# Printrhub_Rev_0_4.net
KiCad netlist of a schematic drawn in EAGLE
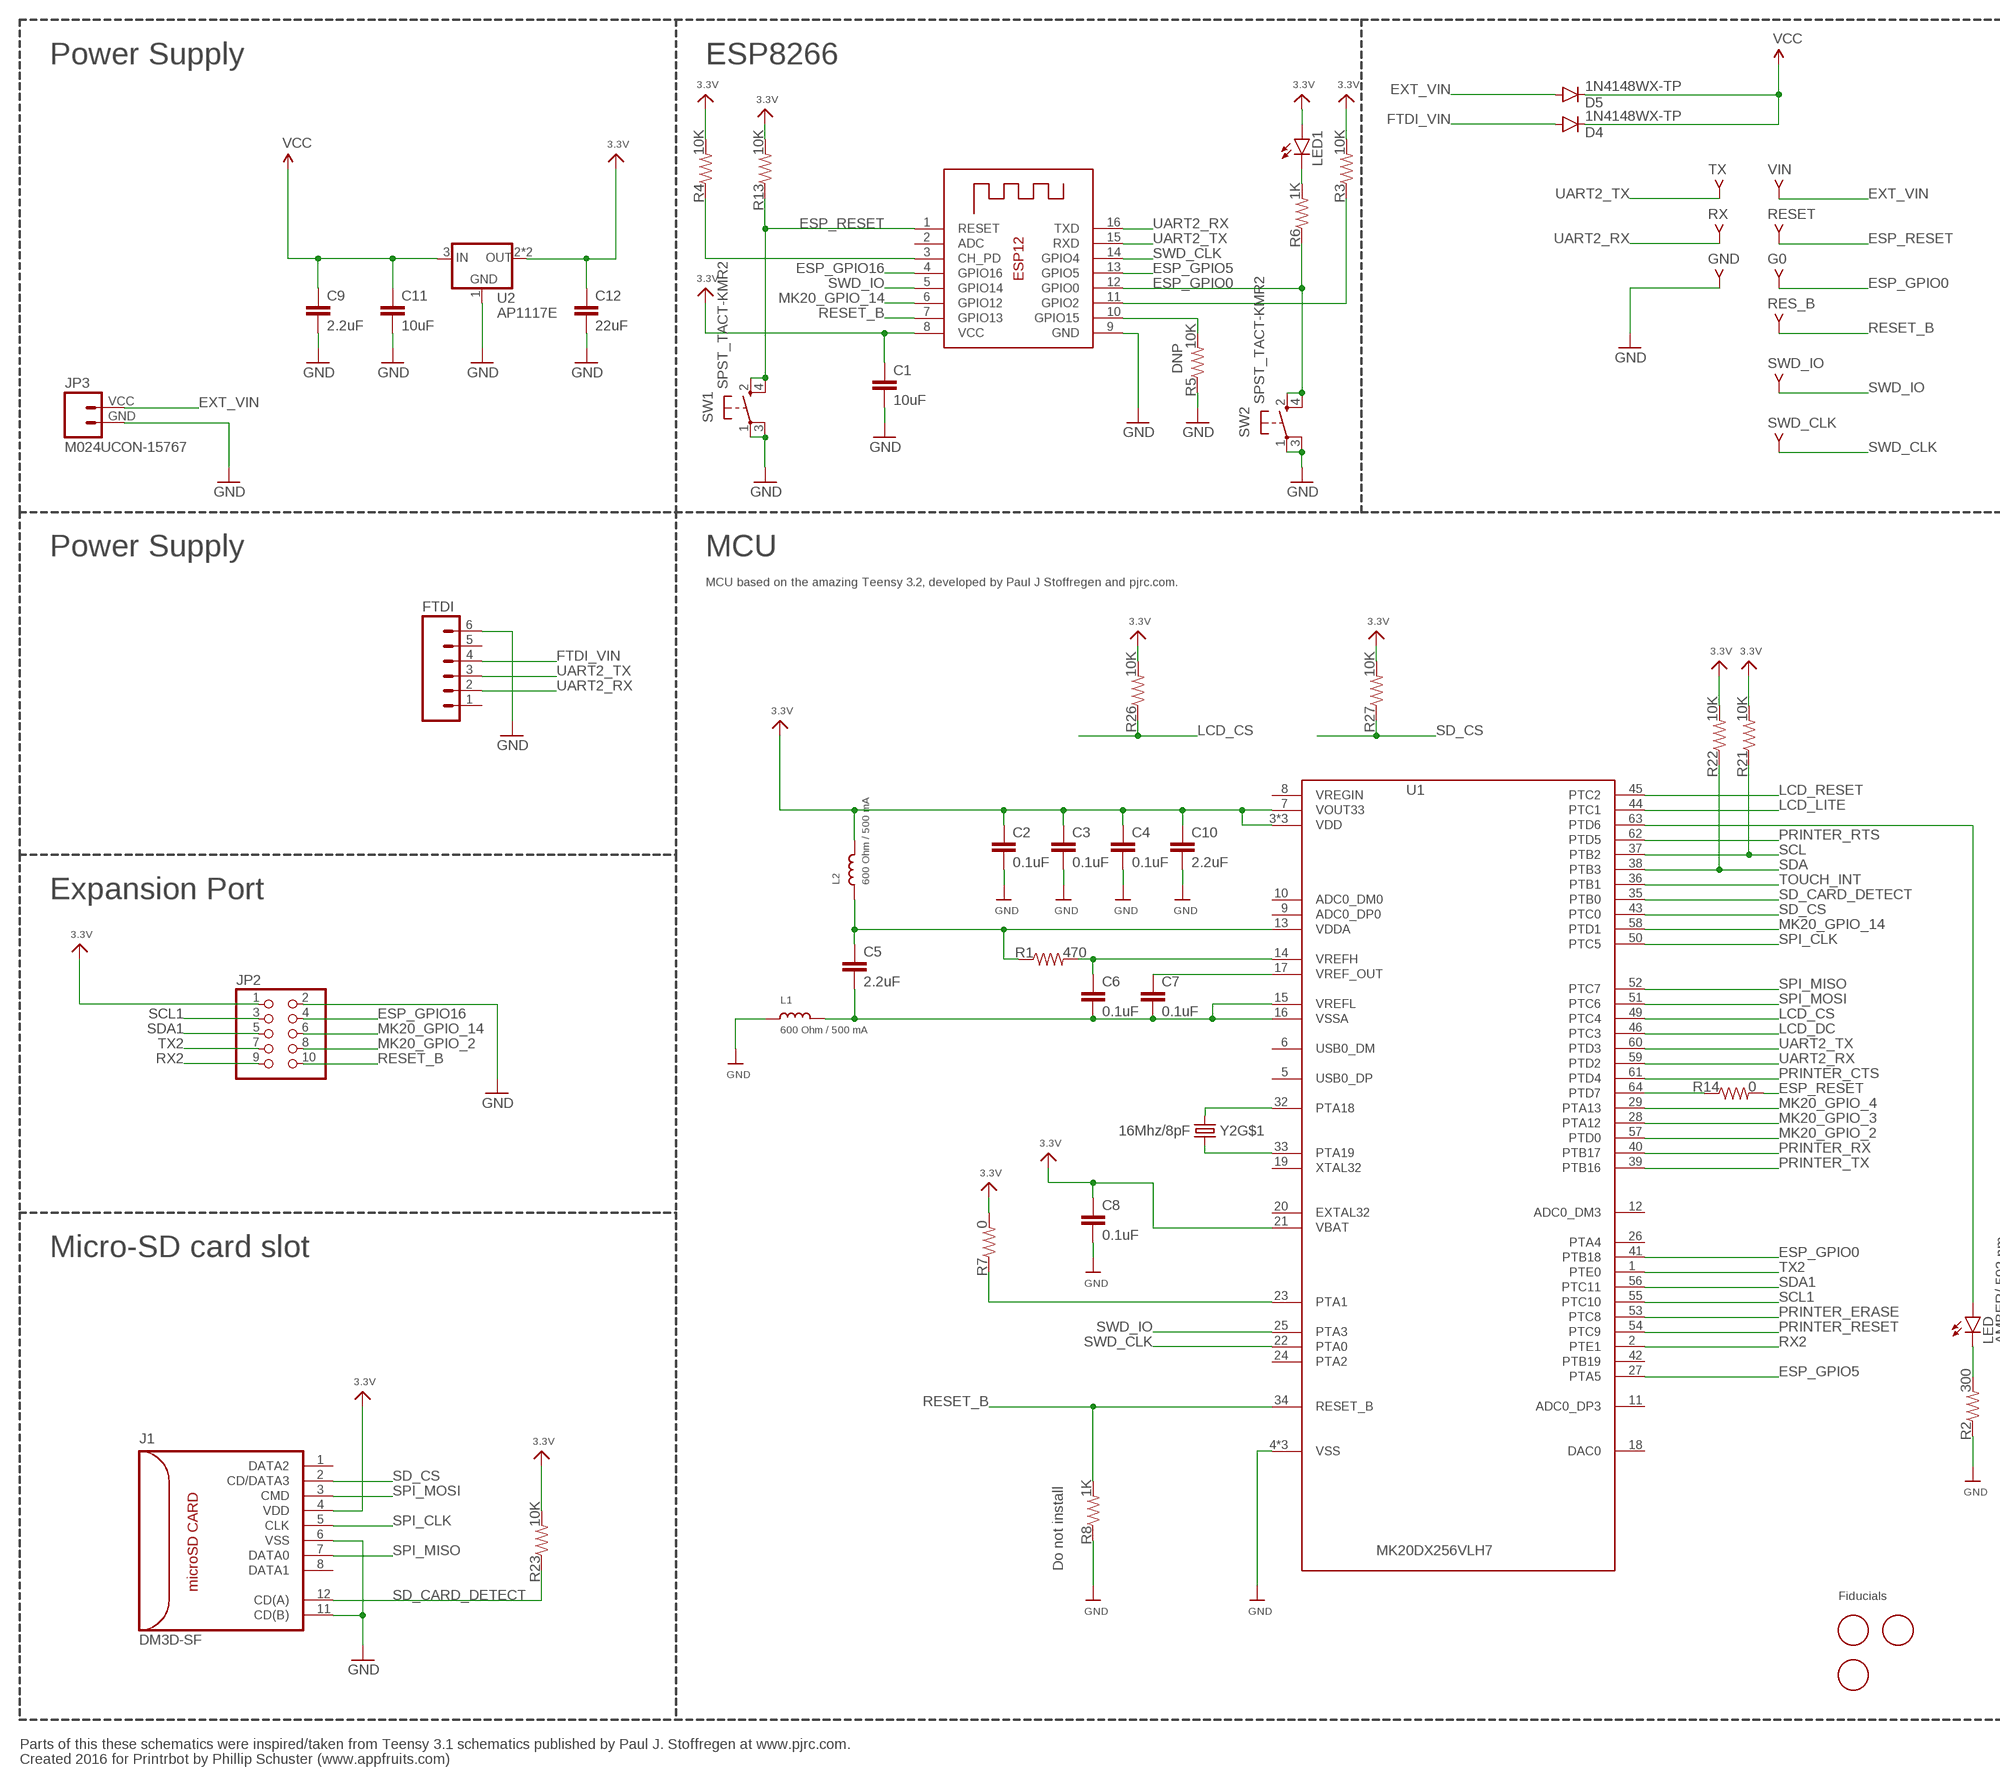
[diagram p0: schematic, sheet 1, part 1 of 2]
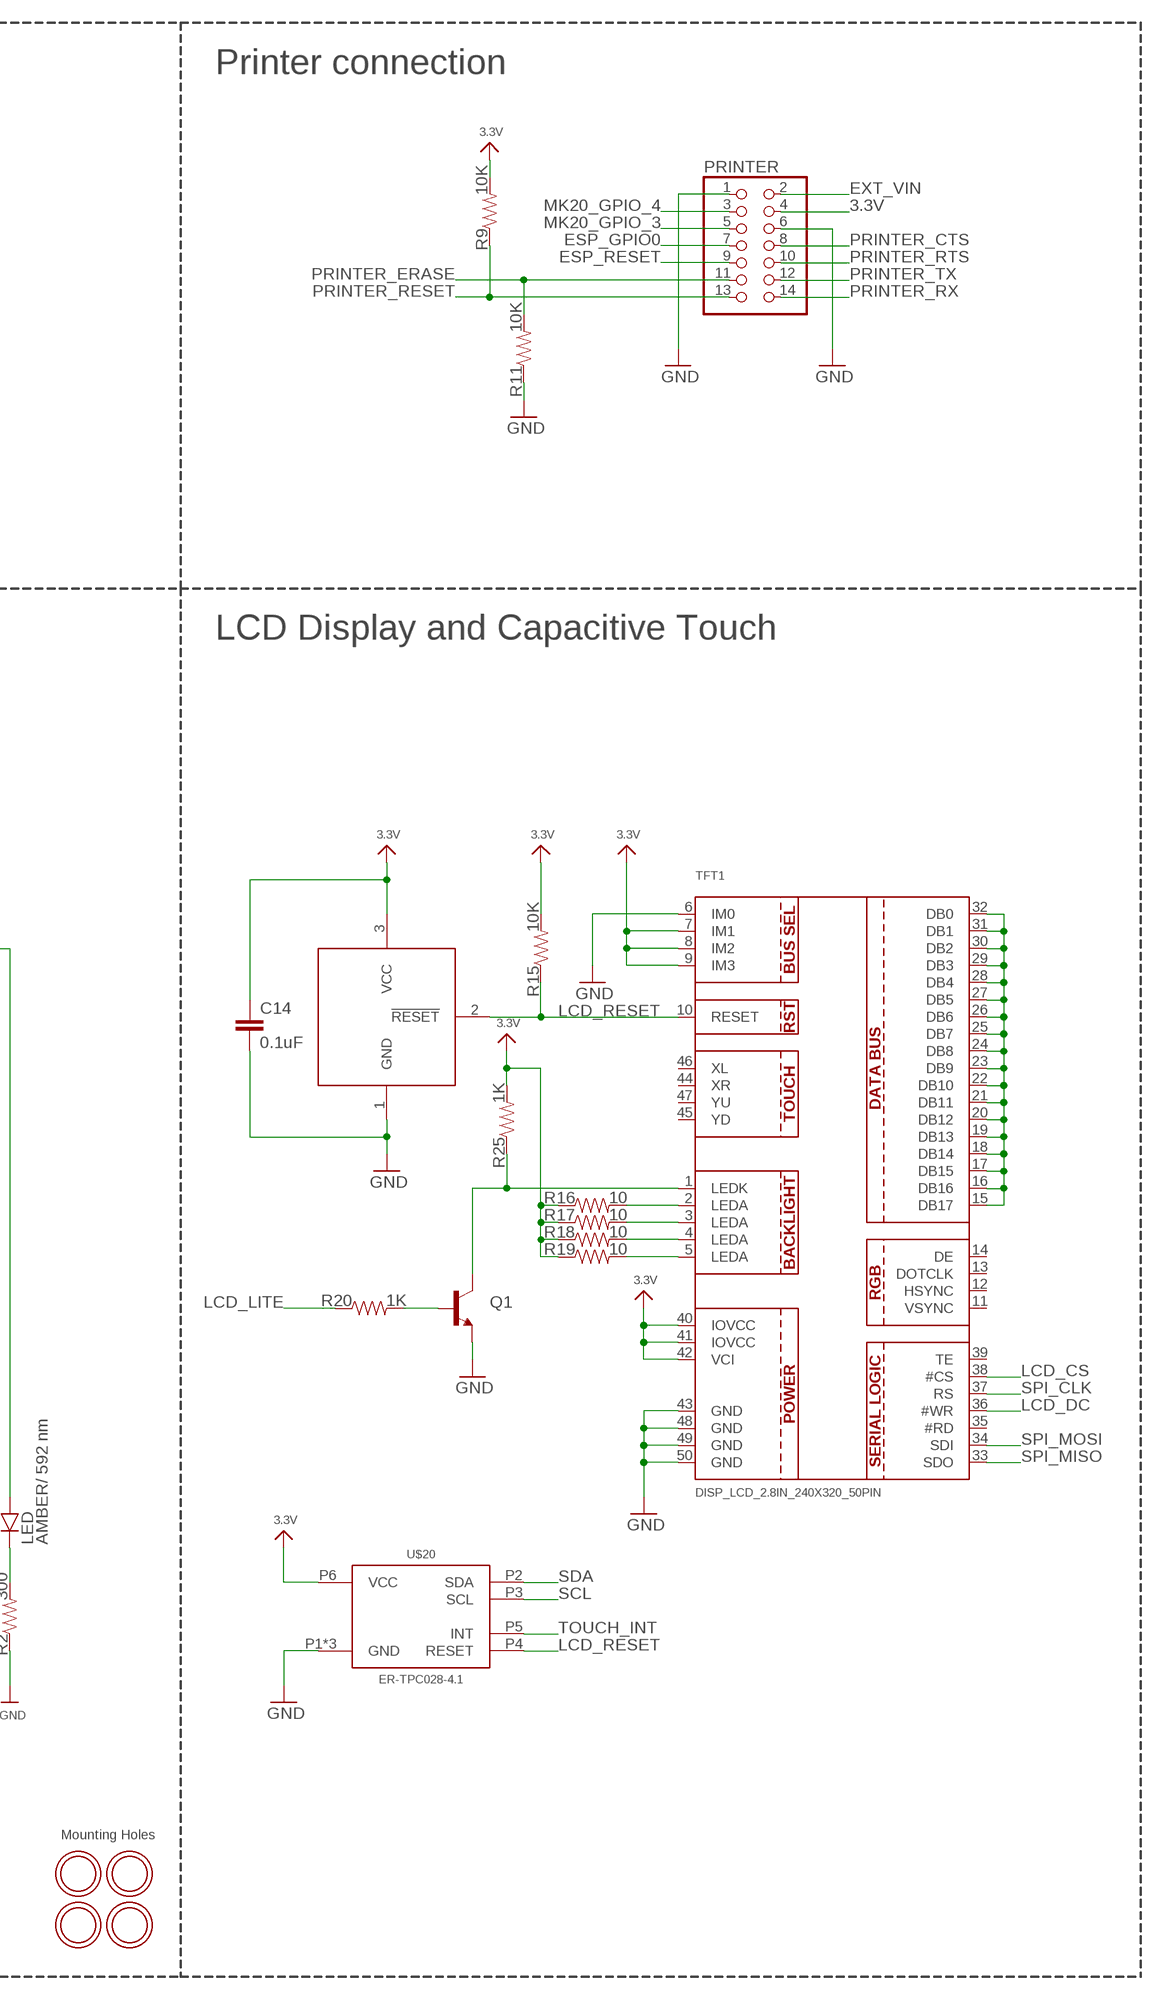
[diagram p1: schematic, sheet 1, part 2 of 2]

(export (version "E")
  (design (tool "Eeschema 10.0.6"))
  (components
    (comp (ref "C1")
      (value "10uF")
      (footprint "eagle-import:0603-CAP")
      (fields (field (name "MF") "Murata") (field (name "MPN") "GRM188R60J106ME47D"))
      (libsource (lib "eagle-import") (part "CAPACITOR-10UF"))
    )
    (comp (ref "C2")
      (value "0.1uF")
      (footprint "eagle-import:0603-CAP")
      (fields (field (name "MF") "Kemet") (field (name "MPN") "C0603C104J3RACTU"))
      (libsource (lib "eagle-import") (part "CAPACITOR-0.1UF"))
    )
    (comp (ref "C3")
      (value "0.1uF")
      (footprint "eagle-import:0603-CAP")
      (fields (field (name "MF") "Kemet") (field (name "MPN") "C0603C104J3RACTU"))
      (libsource (lib "eagle-import") (part "CAPACITOR-0.1UF"))
    )
    (comp (ref "C4")
      (value "0.1uF")
      (footprint "eagle-import:0603-CAP")
      (fields (field (name "MF") "Kemet") (field (name "MPN") "C0603C104J3RACTU"))
      (libsource (lib "eagle-import") (part "CAPACITOR-0.1UF"))
    )
    (comp (ref "C5")
      (value "2.2uF")
      (footprint "eagle-import:0603-CAP")
      (fields (field (name "MF") "Kemet") (field (name "MPN") "C0603C225K4PACTU"))
      (libsource (lib "eagle-import") (part "CAPACITOR-2.2UF"))
    )
    (comp (ref "C6")
      (value "0.1uF")
      (footprint "eagle-import:0603-CAP")
      (fields (field (name "MF") "Kemet") (field (name "MPN") "C0603C104J3RACTU"))
      (libsource (lib "eagle-import") (part "CAPACITOR-0.1UF"))
    )
    (comp (ref "C7")
      (value "0.1uF")
      (footprint "eagle-import:0603-CAP")
      (fields (field (name "MF") "Kemet") (field (name "MPN") "C0603C104J3RACTU"))
      (libsource (lib "eagle-import") (part "CAPACITOR-0.1UF"))
    )
    (comp (ref "C8")
      (value "0.1uF")
      (footprint "eagle-import:0603-CAP")
      (fields (field (name "MF") "Kemet") (field (name "MPN") "C0603C104J3RACTU"))
      (libsource (lib "eagle-import") (part "CAPACITOR-0.1UF"))
    )
    (comp (ref "C9")
      (value "2.2uF")
      (footprint "eagle-import:0603-CAP")
      (fields (field (name "MF") "Kemet") (field (name "MPN") "C0603C225K4PACTU"))
      (libsource (lib "eagle-import") (part "CAPACITOR-2.2UF"))
    )
    (comp (ref "C10")
      (value "2.2uF")
      (footprint "eagle-import:0603-CAP")
      (fields (field (name "MF") "Kemet") (field (name "MPN") "C0603C225K4PACTU"))
      (libsource (lib "eagle-import") (part "CAPACITOR-2.2UF"))
    )
    (comp (ref "C11")
      (value "10uF")
      (footprint "eagle-import:0603-CAP")
      (fields (field (name "MF") "Murata") (field (name "MPN") "GRM188R60J106ME47D"))
      (libsource (lib "eagle-import") (part "CAPACITOR-10UF"))
    )
    (comp (ref "C12")
      (value "22uF")
      (footprint "eagle-import:0603-CAP")
      (fields (field (name "MF") "Murata") (field (name "MPN") "GRM188R60J226MEA0D"))
      (libsource (lib "eagle-import") (part "CAPACITOR-22UF"))
    )
    (comp (ref "C14")
      (value "0.1uF")
      (footprint "eagle-import:0603-CAP")
      (fields (field (name "MF") "Kemet") (field (name "MPN") "C0603C104J3RACTU"))
      (libsource (lib "eagle-import") (part "CAPACITOR-0.1UF"))
    )
    (comp (ref "D4")
      (value "1N4148WX-TP")
      (footprint "eagle-import:SOD-323")
      (fields (field (name "MF") "Micro Commercial Co"))
      (libsource (lib "eagle-import") (part "DIODESOD"))
    )
    (comp (ref "D5")
      (value "1N4148WX-TP")
      (footprint "eagle-import:SOD-323")
      (fields (field (name "MF") "Micro Commercial Co"))
      (libsource (lib "eagle-import") (part "DIODESOD"))
    )
    (comp (ref "FTDI")
      (value "M06SMD-STRAIGHT-ALT")
      (footprint "eagle-import:1X06_SMD_STRAIGHT_ALT")
      (libsource (lib "eagle-import") (part "M06SMD-STRAIGHT-ALT"))
    )
    (comp (ref "G0")
      (value "TPV-SMD-18RN")
      (footprint "eagle-import:SMD-18RN")
      (libsource (lib "eagle-import") (part "TPV-SMD-18RN"))
    )
    (comp (ref "GND")
      (value "TPV-SMD-18RN")
      (footprint "eagle-import:SMD-18RN")
      (libsource (lib "eagle-import") (part "TPV-SMD-18RN"))
    )
    (comp (ref "J1")
      (value "DM3D-SF")
      (footprint "eagle-import:DM3D-SF")
      (libsource (lib "eagle-import") (part "DM3D-SF"))
    )
    (comp (ref "JP2")
      (value "PINHD-2X5SMT")
      (footprint "eagle-import:2X05_SMT")
      (libsource (lib "eagle-import") (part "PINHD-2X5SMT"))
    )
    (comp (ref "JP3")
      (value "M024UCON-15767")
      (footprint "eagle-import:JST-2-SMD-VERT")
      (libsource (lib "eagle-import") (part "M024UCON-15767"))
    )
    (comp (ref "L1")
      (value "600 Ohm / 500 mA")
      (footprint "eagle-import:0603")
      (fields (field (name "MF") "Murata") (field (name "MPN") "BLM18AG601SN1D"))
      (libsource (lib "eagle-import") (part "INDUCTOR-0603_600OHM/500MA"))
    )
    (comp (ref "L2")
      (value "600 Ohm / 500 mA")
      (footprint "eagle-import:0603")
      (fields (field (name "MF") "Murata") (field (name "MPN") "BLM18AG601SN1D"))
      (libsource (lib "eagle-import") (part "INDUCTOR-0603_600OHM/500MA"))
    )
    (comp (ref "LED")
      (value "AMBER/ 592 nm")
      (footprint "eagle-import:LED-0603")
      (fields (field (name "MF") "Avago Technologies") (field (name "MPN") "HSMA-C190"))
      (libsource (lib "eagle-import") (part "LED-AMBER"))
    )
    (comp (ref "LED1")
      (value "LED-GREEN")
      (footprint "eagle-import:LED-0603")
      (fields (field (name "MF") "Avago") (field (name "MPN") "HSMG-C190"))
      (libsource (lib "eagle-import") (part "LED-GREEN"))
    )
    (comp (ref "PRINTER")
      (value "PINHD-2X7SMT")
      (footprint "eagle-import:2X07_SMT")
      (libsource (lib "eagle-import") (part "PINHD-2X7SMT"))
    )
    (comp (ref "Q1")
      (value "TRANSISTOR_NPNSOT23-3")
      (footprint "eagle-import:SOT23-3")
      (fields (field (name "MF") "ON Semiconductor") (field (name "MPN") "MMBT2222ALT1G"))
      (libsource (lib "eagle-import") (part "TRANSISTOR_NPNSOT23-3"))
    )
    (comp (ref "R1")
      (value "470")
      (footprint "eagle-import:0603-RES")
      (fields (field (name "MF") "Panasonic") (field (name "MPN") "ERJ-3GEYJ471V"))
      (libsource (lib "eagle-import") (part "RESISTOR-470"))
    )
    (comp (ref "R2")
      (value "300")
      (footprint "eagle-import:0603-RES")
      (libsource (lib "eagle-import") (part "RESISTOR0603"))
    )
    (comp (ref "R3")
      (value "10K")
      (footprint "eagle-import:0603-RES")
      (fields (field (name "MF") "Panasonic") (field (name "MPN") "ERJ-3GEYJ103V"))
      (libsource (lib "eagle-import") (part "RESISTOR-10K"))
    )
    (comp (ref "R4")
      (value "10K")
      (footprint "eagle-import:0603-RES")
      (fields (field (name "MF") "Panasonic") (field (name "MPN") "ERJ-3GEYJ103V"))
      (libsource (lib "eagle-import") (part "RESISTOR-10K"))
    )
    (comp (ref "R5")
      (value "10K")
      (footprint "eagle-import:0603-RES")
      (fields (field (name "MF") "Panasonic") (field (name "MPN") "ERJ-3GEYJ103V"))
      (libsource (lib "eagle-import") (part "RESISTOR-10K"))
    )
    (comp (ref "R6")
      (value "1K")
      (footprint "eagle-import:0603-RES")
      (fields (field (name "MF") "Panasonic") (field (name "MPN") "ERJ-3GEYJ102V"))
      (libsource (lib "eagle-import") (part "RESISTOR-1K"))
    )
    (comp (ref "R7")
      (value "0")
      (footprint "eagle-import:0603-RES")
      (fields (field (name "MF") "Panasonic") (field (name "MPN") "ERJ-3GEY0R00V"))
      (libsource (lib "eagle-import") (part "RESISTOR-0"))
    )
    (comp (ref "R8")
      (value "1K")
      (footprint "eagle-import:0603-RES")
      (fields (field (name "MF") "Panasonic") (field (name "MPN") "ERJ-3GEYJ102V"))
      (libsource (lib "eagle-import") (part "RESISTOR-1K"))
    )
    (comp (ref "R9")
      (value "10K")
      (footprint "eagle-import:0603-RES")
      (fields (field (name "MF") "Panasonic") (field (name "MPN") "ERJ-3GEYJ103V"))
      (libsource (lib "eagle-import") (part "RESISTOR-10K"))
    )
    (comp (ref "R11")
      (value "10K")
      (footprint "eagle-import:0603-RES")
      (fields (field (name "MF") "Panasonic") (field (name "MPN") "ERJ-3GEYJ103V"))
      (libsource (lib "eagle-import") (part "RESISTOR-10K"))
    )
    (comp (ref "R13")
      (value "10K")
      (footprint "eagle-import:0603-RES")
      (fields (field (name "MF") "Panasonic") (field (name "MPN") "ERJ-3GEYJ103V"))
      (libsource (lib "eagle-import") (part "RESISTOR-10K"))
    )
    (comp (ref "R14")
      (value "0")
      (footprint "eagle-import:0603-RES")
      (fields (field (name "MF") "Panasonic") (field (name "MPN") "ERJ-3GEY0R00V"))
      (libsource (lib "eagle-import") (part "RESISTOR-0"))
    )
    (comp (ref "R15")
      (value "10K")
      (footprint "eagle-import:0603-RES")
      (fields (field (name "MF") "Panasonic") (field (name "MPN") "ERJ-3GEYJ103V"))
      (libsource (lib "eagle-import") (part "RESISTOR-10K"))
    )
    (comp (ref "R16")
      (value "10")
      (footprint "eagle-import:0603-RES")
      (fields (field (name "MF") "Panasonic") (field (name "MPN") "ERJ-3EKF10R0V"))
      (libsource (lib "eagle-import") (part "RESISTOR-10"))
    )
    (comp (ref "R17")
      (value "10")
      (footprint "eagle-import:0603-RES")
      (fields (field (name "MF") "Panasonic") (field (name "MPN") "ERJ-3EKF10R0V"))
      (libsource (lib "eagle-import") (part "RESISTOR-10"))
    )
    (comp (ref "R18")
      (value "10")
      (footprint "eagle-import:0603-RES")
      (fields (field (name "MF") "Panasonic") (field (name "MPN") "ERJ-3EKF10R0V"))
      (libsource (lib "eagle-import") (part "RESISTOR-10"))
    )
    (comp (ref "R19")
      (value "10")
      (footprint "eagle-import:0603-RES")
      (fields (field (name "MF") "Panasonic") (field (name "MPN") "ERJ-3EKF10R0V"))
      (libsource (lib "eagle-import") (part "RESISTOR-10"))
    )
    (comp (ref "R20")
      (value "1K")
      (footprint "eagle-import:0603-RES")
      (fields (field (name "MF") "Panasonic") (field (name "MPN") "ERJ-3GEYJ102V"))
      (libsource (lib "eagle-import") (part "RESISTOR-1K"))
    )
    (comp (ref "R21")
      (value "10K")
      (footprint "eagle-import:0603-RES")
      (fields (field (name "MF") "Panasonic") (field (name "MPN") "ERJ-3GEYJ103V"))
      (libsource (lib "eagle-import") (part "RESISTOR-10K"))
    )
    (comp (ref "R22")
      (value "10K")
      (footprint "eagle-import:0603-RES")
      (fields (field (name "MF") "Panasonic") (field (name "MPN") "ERJ-3GEYJ103V"))
      (libsource (lib "eagle-import") (part "RESISTOR-10K"))
    )
    (comp (ref "R23")
      (value "10K")
      (footprint "eagle-import:0603-RES")
      (fields (field (name "MF") "Panasonic") (field (name "MPN") "ERJ-3GEYJ103V"))
      (libsource (lib "eagle-import") (part "RESISTOR-10K"))
    )
    (comp (ref "R25")
      (value "1K")
      (footprint "eagle-import:0603-RES")
      (fields (field (name "MF") "Panasonic") (field (name "MPN") "ERJ-3GEYJ102V"))
      (libsource (lib "eagle-import") (part "RESISTOR-1K"))
    )
    (comp (ref "R26")
      (value "10K")
      (footprint "eagle-import:0603-RES")
      (fields (field (name "MF") "Panasonic") (field (name "MPN") "ERJ-3GEYJ103V"))
      (libsource (lib "eagle-import") (part "RESISTOR-10K"))
    )
    (comp (ref "R27")
      (value "10K")
      (footprint "eagle-import:0603-RES")
      (fields (field (name "MF") "Panasonic") (field (name "MPN") "ERJ-3GEYJ103V"))
      (libsource (lib "eagle-import") (part "RESISTOR-10K"))
    )
    (comp (ref "RESET")
      (value "TPV-SMD-18RN")
      (footprint "eagle-import:SMD-18RN")
      (libsource (lib "eagle-import") (part "TPV-SMD-18RN"))
    )
    (comp (ref "RES_B")
      (value "TPV-SMD-18RN")
      (footprint "eagle-import:SMD-18RN")
      (libsource (lib "eagle-import") (part "TPV-SMD-18RN"))
    )
    (comp (ref "RX")
      (value "TPV-SMD-18RN")
      (footprint "eagle-import:SMD-18RN")
      (libsource (lib "eagle-import") (part "TPV-SMD-18RN"))
    )
    (comp (ref "SW1")
      (value "SPST_TACT-KMR2")
      (footprint "eagle-import:KMR2")
      (libsource (lib "eagle-import") (part "SPST_TACT-KMR2"))
    )
    (comp (ref "SW2")
      (value "SPST_TACT-KMR2")
      (footprint "eagle-import:KMR2")
      (libsource (lib "eagle-import") (part "SPST_TACT-KMR2"))
    )
    (comp (ref "SWD_CLK")
      (value "TPV-SMD-18RN")
      (footprint "eagle-import:SMD-18RN")
      (libsource (lib "eagle-import") (part "TPV-SMD-18RN"))
    )
    (comp (ref "SWD_IO")
      (value "TPV-SMD-18RN")
      (footprint "eagle-import:SMD-18RN")
      (libsource (lib "eagle-import") (part "TPV-SMD-18RN"))
    )
    (comp (ref "TFT1")
      (value "DISP_LCD_2.8IN_240X320_50PIN")
      (footprint "eagle-import:TFT_2.83IN_240X320_50PIN")
      (libsource (lib "eagle-import") (part "DISP_LCD_2.8IN_240X320_50PIN"))
    )
    (comp (ref "TX")
      (value "TPV-SMD-18RN")
      (footprint "eagle-import:SMD-18RN")
      (libsource (lib "eagle-import") (part "TPV-SMD-18RN"))
    )
    (comp (ref "U$15")
      (value "MOUNTINGHOLE")
      (footprint "eagle-import:HOLE_M3.0")
      (libsource (lib "eagle-import") (part "MOUNTINGHOLE"))
    )
    (comp (ref "U$16")
      (value "MOUNTINGHOLE")
      (footprint "eagle-import:HOLE_M3.0")
      (libsource (lib "eagle-import") (part "MOUNTINGHOLE"))
    )
    (comp (ref "U$17")
      (value "MOUNTINGHOLE")
      (footprint "eagle-import:HOLE_M3.0")
      (libsource (lib "eagle-import") (part "MOUNTINGHOLE"))
    )
    (comp (ref "U$18")
      (value "MOUNTINGHOLE")
      (footprint "eagle-import:HOLE_M3.0")
      (libsource (lib "eagle-import") (part "MOUNTINGHOLE"))
    )
    (comp (ref "U$20")
      (value "ER-TPC028-4.1")
      (footprint "eagle-import:ER-CON06HB-1")
      (libsource (lib "eagle-import") (part "ER-TPC028-4.1"))
    )
    (comp (ref "U$38")
      (value "FIDUCIAL")
      (footprint "eagle-import:FIDUCIAL_1MM")
      (libsource (lib "eagle-import") (part "FIDUCIAL"))
    )
    (comp (ref "U$39")
      (value "FIDUCIAL")
      (footprint "eagle-import:FIDUCIAL_1MM")
      (libsource (lib "eagle-import") (part "FIDUCIAL"))
    )
    (comp (ref "U$40")
      (value "FIDUCIAL")
      (footprint "eagle-import:FIDUCIAL_1MM")
      (libsource (lib "eagle-import") (part "FIDUCIAL"))
    )
    (comp (ref "U1")
      (value "MK20DX256VLH7")
      (footprint "eagle-import:MK20DX256VLH7")
      (fields (field (name "MF") "Freescale"))
      (libsource (lib "eagle-import") (part "MK20DX256VLH7"))
    )
    (comp (ref "U2")
      (value "AP1117E")
      (footprint "eagle-import:SOT223")
      (libsource (lib "eagle-import") (part "AP1117E"))
    )
    (comp (ref "U3")
      (value "MAX308-SOT23")
      (footprint "eagle-import:SOT23")
      (libsource (lib "eagle-import") (part "MAX308-SOT23"))
    )
    (comp (ref "VIN")
      (value "TPV-SMD-18RN")
      (footprint "eagle-import:SMD-18RN")
      (libsource (lib "eagle-import") (part "TPV-SMD-18RN"))
    )
    (comp (ref "X1")
      (value "ESP-12")
      (footprint "eagle-import:ESP-12")
      (libsource (lib "eagle-import") (part "ESP-12"))
    )
    (comp (ref "Y2")
      (value "16Mhz/8pF")
      (footprint "eagle-import:CRYSTAL-SMD-5X3")
      (fields (field (name "MF") "ECS") (field (name "MPN") "ECS-160-8-30B-CKM"))
      (libsource (lib "eagle-import") (part "CRYSTAL/SMD-5X3-GND16MHZ/8PF"))
    )
  )
  (nets
    (net (code "1") (name "/ESP_GPIO0") (class "Default")
      (node (ref "G0") (pin "TP") (pinfunction "TP_TP") (pintype "passive"))
      (node (ref "PRINTER") (pin "7") (pinfunction "7_7") (pintype "passive"))
      (node (ref "R6") (pin "1") (pinfunction "1_1") (pintype "passive"))
      (node (ref "SW2") (pin "2") (pinfunction "S_2") (pintype "passive"))
      (node (ref "SW2") (pin "4") (pinfunction "S1_4") (pintype "passive"))
      (node (ref "U1") (pin "41") (pinfunction "PTB18_41") (pintype "bidirectional"))
      (node (ref "X1") (pin "12") (pinfunction "GPIO0_12") (pintype "bidirectional"))
    )
    (net (code "2") (name "/ESP_GPIO5") (class "Default")
      (node (ref "U1") (pin "27") (pinfunction "PTA5_27") (pintype "bidirectional"))
      (node (ref "X1") (pin "13") (pinfunction "GPIO5_13") (pintype "bidirectional"))
    )
    (net (code "3") (name "/ESP_GPIO16") (class "Default")
      (node (ref "JP2") (pin "4") (pinfunction "4_4") (pintype "passive"))
      (node (ref "X1") (pin "4") (pinfunction "GPIO16_4") (pintype "bidirectional"))
    )
    (net (code "4") (name "/ESP_RESET") (class "Default")
      (node (ref "PRINTER") (pin "9") (pinfunction "9_9") (pintype "passive"))
      (node (ref "R13") (pin "1") (pinfunction "1_1") (pintype "passive"))
      (node (ref "R14") (pin "2") (pinfunction "2_2") (pintype "passive"))
      (node (ref "RESET") (pin "TP") (pinfunction "TP_TP") (pintype "passive"))
      (node (ref "SW1") (pin "2") (pinfunction "S_2") (pintype "passive"))
      (node (ref "SW1") (pin "4") (pinfunction "S1_4") (pintype "passive"))
      (node (ref "X1") (pin "1") (pinfunction "RESET_1") (pintype "input"))
    )
    (net (code "5") (name "/EXT_VIN") (class "Default")
      (node (ref "D5") (pin "A") (pinfunction "A_A") (pintype "passive"))
      (node (ref "JP3") (pin "VCC") (pinfunction "2_VCC") (pintype "passive"))
      (node (ref "PRINTER") (pin "2") (pinfunction "2_2") (pintype "passive"))
      (node (ref "VIN") (pin "TP") (pinfunction "TP_TP") (pintype "passive"))
    )
    (net (code "6") (name "/FTDI_VIN") (class "Default")
      (node (ref "D4") (pin "A") (pinfunction "A_A") (pintype "passive"))
      (node (ref "FTDI") (pin "4") (pinfunction "4_4") (pintype "passive"))
    )
    (net (code "7") (name "/LCD_CS") (class "Default")
      (node (ref "R26") (pin "1") (pinfunction "1_1") (pintype "passive"))
      (node (ref "TFT1") (pin "38") (pinfunction "#CS_38") (pintype "bidirectional"))
      (node (ref "U1") (pin "49") (pinfunction "PTC4_49") (pintype "bidirectional"))
    )
    (net (code "8") (name "/LCD_DC") (class "Default")
      (node (ref "TFT1") (pin "36") (pinfunction "#WR_36") (pintype "bidirectional"))
      (node (ref "U1") (pin "46") (pinfunction "PTC3_46") (pintype "bidirectional"))
    )
    (net (code "9") (name "/LCD_LITE") (class "Default")
      (node (ref "R20") (pin "1") (pinfunction "1_1") (pintype "passive"))
      (node (ref "U1") (pin "44") (pinfunction "PTC1_44") (pintype "bidirectional"))
    )
    (net (code "10") (name "/LCD_RESET") (class "Default")
      (node (ref "R15") (pin "1") (pinfunction "1_1") (pintype "passive"))
      (node (ref "TFT1") (pin "10") (pinfunction "RESET_10") (pintype "bidirectional"))
      (node (ref "U$20") (pin "P4") (pinfunction "RESET_P4") (pintype "bidirectional"))
      (node (ref "U1") (pin "45") (pinfunction "PTC2_45") (pintype "bidirectional"))
      (node (ref "U3") (pin "2") (pinfunction "~{RESET}_2") (pintype "bidirectional"))
    )
    (net (code "11") (name "/MK20_GPIO_2") (class "Default")
      (node (ref "JP2") (pin "8") (pinfunction "8_8") (pintype "passive"))
      (node (ref "U1") (pin "57") (pinfunction "PTD0_57") (pintype "bidirectional"))
    )
    (net (code "12") (name "/MK20_GPIO_3") (class "Default")
      (node (ref "PRINTER") (pin "5") (pinfunction "5_5") (pintype "passive"))
      (node (ref "U1") (pin "28") (pinfunction "PTA12_28") (pintype "bidirectional"))
    )
    (net (code "13") (name "/MK20_GPIO_4") (class "Default")
      (node (ref "PRINTER") (pin "3") (pinfunction "3_3") (pintype "passive"))
      (node (ref "U1") (pin "29") (pinfunction "PTA13_29") (pintype "bidirectional"))
    )
    (net (code "14") (name "/MK20_GPIO_14") (class "Default")
      (node (ref "JP2") (pin "6") (pinfunction "6_6") (pintype "passive"))
      (node (ref "U1") (pin "58") (pinfunction "PTD1_58") (pintype "bidirectional"))
      (node (ref "X1") (pin "6") (pinfunction "GPIO12_6") (pintype "bidirectional"))
    )
    (net (code "15") (name "/PRINTER_CTS") (class "Default")
      (node (ref "PRINTER") (pin "8") (pinfunction "8_8") (pintype "passive"))
      (node (ref "U1") (pin "61") (pinfunction "PTD4_61") (pintype "bidirectional"))
    )
    (net (code "16") (name "/PRINTER_ERASE") (class "Default")
      (node (ref "PRINTER") (pin "11") (pinfunction "11_11") (pintype "passive"))
      (node (ref "R11") (pin "2") (pinfunction "2_2") (pintype "passive"))
      (node (ref "U1") (pin "53") (pinfunction "PTC8_53") (pintype "bidirectional"))
    )
    (net (code "17") (name "/PRINTER_RESET") (class "Default")
      (node (ref "PRINTER") (pin "13") (pinfunction "13_13") (pintype "passive"))
      (node (ref "R9") (pin "1") (pinfunction "1_1") (pintype "passive"))
      (node (ref "U1") (pin "54") (pinfunction "PTC9_54") (pintype "bidirectional"))
    )
    (net (code "18") (name "/PRINTER_RTS") (class "Default")
      (node (ref "PRINTER") (pin "10") (pinfunction "10_10") (pintype "passive"))
      (node (ref "U1") (pin "62") (pinfunction "PTD5_62") (pintype "bidirectional"))
    )
    (net (code "19") (name "/PRINTER_RX") (class "Default")
      (node (ref "PRINTER") (pin "14") (pinfunction "14_14") (pintype "passive"))
      (node (ref "U1") (pin "40") (pinfunction "PTB17_40") (pintype "bidirectional"))
    )
    (net (code "20") (name "/PRINTER_TX") (class "Default")
      (node (ref "PRINTER") (pin "12") (pinfunction "12_12") (pintype "passive"))
      (node (ref "U1") (pin "39") (pinfunction "PTB16_39") (pintype "bidirectional"))
    )
    (net (code "21") (name "/RESET_B") (class "Default")
      (node (ref "JP2") (pin "10") (pinfunction "10_10") (pintype "passive"))
      (node (ref "R8") (pin "2") (pinfunction "2_2") (pintype "passive"))
      (node (ref "RES_B") (pin "TP") (pinfunction "TP_TP") (pintype "passive"))
      (node (ref "U1") (pin "34") (pinfunction "RESET_B_34") (pintype "bidirectional"))
      (node (ref "X1") (pin "7") (pinfunction "GPIO13_7") (pintype "bidirectional"))
    )
    (net (code "22") (name "/RX2") (class "Default")
      (node (ref "JP2") (pin "9") (pinfunction "9_9") (pintype "passive"))
      (node (ref "U1") (pin "2") (pinfunction "PTE1_2") (pintype "bidirectional"))
    )
    (net (code "23") (name "/SCL") (class "Default")
      (node (ref "R21") (pin "1") (pinfunction "1_1") (pintype "passive"))
      (node (ref "U$20") (pin "P3") (pinfunction "SCL_P3") (pintype "bidirectional"))
      (node (ref "U1") (pin "37") (pinfunction "PTB2_37") (pintype "bidirectional"))
    )
    (net (code "24") (name "/SCL1") (class "Default")
      (node (ref "JP2") (pin "3") (pinfunction "3_3") (pintype "passive"))
      (node (ref "U1") (pin "55") (pinfunction "PTC10_55") (pintype "bidirectional"))
    )
    (net (code "25") (name "/SDA") (class "Default")
      (node (ref "R22") (pin "1") (pinfunction "1_1") (pintype "passive"))
      (node (ref "U$20") (pin "P2") (pinfunction "SDA_P2") (pintype "bidirectional"))
      (node (ref "U1") (pin "38") (pinfunction "PTB3_38") (pintype "bidirectional"))
    )
    (net (code "26") (name "/SDA1") (class "Default")
      (node (ref "JP2") (pin "5") (pinfunction "5_5") (pintype "passive"))
      (node (ref "U1") (pin "56") (pinfunction "PTC11_56") (pintype "bidirectional"))
    )
    (net (code "27") (name "/SD_CARD_DETECT") (class "Default")
      (node (ref "J1") (pin "12") (pinfunction "CD(A)_12") (pintype "bidirectional"))
      (node (ref "R23") (pin "1") (pinfunction "1_1") (pintype "passive"))
      (node (ref "U1") (pin "35") (pinfunction "PTB0_35") (pintype "bidirectional"))
    )
    (net (code "28") (name "/SD_CS") (class "Default")
      (node (ref "J1") (pin "2") (pinfunction "CD/DATA3_2") (pintype "bidirectional"))
      (node (ref "R27") (pin "1") (pinfunction "1_1") (pintype "passive"))
      (node (ref "U1") (pin "43") (pinfunction "PTC0_43") (pintype "bidirectional"))
    )
    (net (code "29") (name "/SPI_CLK") (class "Default")
      (node (ref "J1") (pin "5") (pinfunction "CLK_5") (pintype "bidirectional"))
      (node (ref "TFT1") (pin "37") (pinfunction "RS_37") (pintype "bidirectional"))
      (node (ref "U1") (pin "50") (pinfunction "PTC5_50") (pintype "bidirectional"))
    )
    (net (code "30") (name "/SPI_MISO") (class "Default")
      (node (ref "J1") (pin "7") (pinfunction "DATA0_7") (pintype "bidirectional"))
      (node (ref "TFT1") (pin "33") (pinfunction "SDO_33") (pintype "bidirectional"))
      (node (ref "U1") (pin "52") (pinfunction "PTC7_52") (pintype "bidirectional"))
    )
    (net (code "31") (name "/SPI_MOSI") (class "Default")
      (node (ref "J1") (pin "3") (pinfunction "CMD_3") (pintype "bidirectional"))
      (node (ref "TFT1") (pin "34") (pinfunction "SDI_34") (pintype "bidirectional"))
      (node (ref "U1") (pin "51") (pinfunction "PTC6_51") (pintype "bidirectional"))
    )
    (net (code "32") (name "/SWD_CLK") (class "Default")
      (node (ref "SWD_CLK") (pin "TP") (pinfunction "TP_TP") (pintype "passive"))
      (node (ref "U1") (pin "22") (pinfunction "PTA0_22") (pintype "bidirectional"))
      (node (ref "X1") (pin "14") (pinfunction "GPIO4_14") (pintype "bidirectional"))
    )
    (net (code "33") (name "/SWD_IO") (class "Default")
      (node (ref "SWD_IO") (pin "TP") (pinfunction "TP_TP") (pintype "passive"))
      (node (ref "U1") (pin "25") (pinfunction "PTA3_25") (pintype "bidirectional"))
      (node (ref "X1") (pin "5") (pinfunction "GPIO14_5") (pintype "bidirectional"))
    )
    (net (code "34") (name "/TOUCH_INT") (class "Default")
      (node (ref "U$20") (pin "P5") (pinfunction "INT_P5") (pintype "bidirectional"))
      (node (ref "U1") (pin "36") (pinfunction "PTB1_36") (pintype "bidirectional"))
    )
    (net (code "35") (name "/TX2") (class "Default")
      (node (ref "JP2") (pin "7") (pinfunction "7_7") (pintype "passive"))
      (node (ref "U1") (pin "1") (pinfunction "PTE0_1") (pintype "bidirectional"))
    )
    (net (code "36") (name "/UART2_RX") (class "Default")
      (node (ref "FTDI") (pin "2") (pinfunction "2_2") (pintype "passive"))
      (node (ref "RX") (pin "TP") (pinfunction "TP_TP") (pintype "passive"))
      (node (ref "U1") (pin "59") (pinfunction "PTD2_59") (pintype "bidirectional"))
      (node (ref "X1") (pin "16") (pinfunction "TXD_16") (pintype "output"))
    )
    (net (code "37") (name "/UART2_TX") (class "Default")
      (node (ref "FTDI") (pin "3") (pinfunction "3_3") (pintype "passive"))
      (node (ref "TX") (pin "TP") (pinfunction "TP_TP") (pintype "passive"))
      (node (ref "U1") (pin "60") (pinfunction "PTD3_60") (pintype "bidirectional"))
      (node (ref "X1") (pin "15") (pinfunction "RXD_15") (pintype "input"))
    )
    (net (code "38") (name "3.3V") (class "Default")
      (node (ref "C1") (pin "1") (pinfunction "1_1") (pintype "passive"))
      (node (ref "C10") (pin "1") (pinfunction "1_1") (pintype "passive"))
      (node (ref "C12") (pin "1") (pinfunction "1_1") (pintype "passive"))
      (node (ref "C14") (pin "1") (pinfunction "1_1") (pintype "passive"))
      (node (ref "C2") (pin "1") (pinfunction "1_1") (pintype "passive"))
      (node (ref "C3") (pin "1") (pinfunction "1_1") (pintype "passive"))
      (node (ref "C4") (pin "1") (pinfunction "1_1") (pintype "passive"))
      (node (ref "C8") (pin "1") (pinfunction "1_1") (pintype "passive"))
      (node (ref "J1") (pin "4") (pinfunction "VDD_4") (pintype "power_in"))
      (node (ref "JP2") (pin "1") (pinfunction "1_1") (pintype "passive"))
      (node (ref "L2") (pin "2") (pinfunction "2_2") (pintype "passive"))
      (node (ref "LED1") (pin "A") (pinfunction "A_A") (pintype "passive"))
      (node (ref "PRINTER") (pin "4") (pinfunction "4_4") (pintype "passive"))
      (node (ref "R13") (pin "2") (pinfunction "2_2") (pintype "passive"))
      (node (ref "R15") (pin "2") (pinfunction "2_2") (pintype "passive"))
      (node (ref "R16") (pin "1") (pinfunction "1_1") (pintype "passive"))
      (node (ref "R17") (pin "1") (pinfunction "1_1") (pintype "passive"))
      (node (ref "R18") (pin "1") (pinfunction "1_1") (pintype "passive"))
      (node (ref "R19") (pin "1") (pinfunction "1_1") (pintype "passive"))
      (node (ref "R21") (pin "2") (pinfunction "2_2") (pintype "passive"))
      (node (ref "R22") (pin "2") (pinfunction "2_2") (pintype "passive"))
      (node (ref "R23") (pin "2") (pinfunction "2_2") (pintype "passive"))
      (node (ref "R25") (pin "2") (pinfunction "2_2") (pintype "passive"))
      (node (ref "R26") (pin "2") (pinfunction "2_2") (pintype "passive"))
      (node (ref "R27") (pin "2") (pinfunction "2_2") (pintype "passive"))
      (node (ref "R3") (pin "2") (pinfunction "2_2") (pintype "passive"))
      (node (ref "R4") (pin "2") (pinfunction "2_2") (pintype "passive"))
      (node (ref "R7") (pin "2") (pinfunction "2_2") (pintype "passive"))
      (node (ref "R9") (pin "2") (pinfunction "2_2") (pintype "passive"))
      (node (ref "TFT1") (pin "40") (pinfunction "IOVCC_40") (pintype "bidirectional"))
      (node (ref "TFT1") (pin "41") (pinfunction "IOVCC_41") (pintype "bidirectional"))
      (node (ref "TFT1") (pin "42") (pinfunction "VCI_42") (pintype "bidirectional"))
      (node (ref "TFT1") (pin "7") (pinfunction "IM1_7") (pintype "bidirectional"))
      (node (ref "TFT1") (pin "8") (pinfunction "IM2_8") (pintype "bidirectional"))
      (node (ref "TFT1") (pin "9") (pinfunction "IM3_9") (pintype "bidirectional"))
      (node (ref "U$20") (pin "P6") (pinfunction "VCC_P6") (pintype "bidirectional"))
      (node (ref "U1") (pin "21") (pinfunction "VBAT_21") (pintype "bidirectional"))
      (node (ref "U1") (pin "3") (pinfunction "VDD_3") (pintype "bidirectional"))
      (node (ref "U1") (pin "30") (pinfunction "VDD_30") (pintype "bidirectional"))
      (node (ref "U1") (pin "48") (pinfunction "VDD_48") (pintype "bidirectional"))
      (node (ref "U1") (pin "7") (pinfunction "VOUT33_7") (pintype "bidirectional"))
      (node (ref "U2") (pin "2") (pinfunction "OUT_2") (pintype "passive"))
      (node (ref "U2") (pin "4") (pinfunction "OUT_4") (pintype "passive"))
      (node (ref "U3") (pin "3") (pinfunction "VCC_3") (pintype "bidirectional"))
      (node (ref "X1") (pin "8") (pinfunction "VCC_8") (pintype "power_in"))
    )
    (net (code "39") (name "GND") (class "Default")
      (node (ref "C1") (pin "2") (pinfunction "2_2") (pintype "passive"))
      (node (ref "C10") (pin "2") (pinfunction "2_2") (pintype "passive"))
      (node (ref "C11") (pin "2") (pinfunction "2_2") (pintype "passive"))
      (node (ref "C12") (pin "2") (pinfunction "2_2") (pintype "passive"))
      (node (ref "C14") (pin "2") (pinfunction "2_2") (pintype "passive"))
      (node (ref "C2") (pin "2") (pinfunction "2_2") (pintype "passive"))
      (node (ref "C3") (pin "2") (pinfunction "2_2") (pintype "passive"))
      (node (ref "C4") (pin "2") (pinfunction "2_2") (pintype "passive"))
      (node (ref "C8") (pin "2") (pinfunction "2_2") (pintype "passive"))
      (node (ref "C9") (pin "2") (pinfunction "2_2") (pintype "passive"))
      (node (ref "FTDI") (pin "6") (pinfunction "6_6") (pintype "passive"))
      (node (ref "GND") (pin "TP") (pinfunction "TP_TP") (pintype "passive"))
      (node (ref "J1") (pin "11") (pinfunction "CD(B)_11") (pintype "bidirectional"))
      (node (ref "J1") (pin "6") (pinfunction "VSS_6") (pintype "power_in"))
      (node (ref "JP2") (pin "2") (pinfunction "2_2") (pintype "passive"))
      (node (ref "JP3") (pin "GND") (pinfunction "1_GND") (pintype "passive"))
      (node (ref "L1") (pin "1") (pinfunction "1_1") (pintype "passive"))
      (node (ref "PRINTER") (pin "1") (pinfunction "1_1") (pintype "passive"))
      (node (ref "PRINTER") (pin "6") (pinfunction "6_6") (pintype "passive"))
      (node (ref "Q1") (pin "2") (pinfunction "E_2") (pintype "passive"))
      (node (ref "R11") (pin "1") (pinfunction "1_1") (pintype "passive"))
      (node (ref "R2") (pin "1") (pinfunction "1_1") (pintype "passive"))
      (node (ref "R5") (pin "1") (pinfunction "1_1") (pintype "passive"))
      (node (ref "R8") (pin "1") (pinfunction "1_1") (pintype "passive"))
      (node (ref "SW1") (pin "1") (pinfunction "P_1") (pintype "passive"))
      (node (ref "SW1") (pin "3") (pinfunction "P1_3") (pintype "passive"))
      (node (ref "SW2") (pin "1") (pinfunction "P_1") (pintype "passive"))
      (node (ref "SW2") (pin "3") (pinfunction "P1_3") (pintype "passive"))
      (node (ref "TFT1") (pin "43") (pinfunction "GND_43") (pintype "bidirectional"))
      (node (ref "TFT1") (pin "48") (pinfunction "GND_48") (pintype "bidirectional"))
      (node (ref "TFT1") (pin "49") (pinfunction "GND_49") (pintype "bidirectional"))
      (node (ref "TFT1") (pin "50") (pinfunction "GND_50") (pintype "bidirectional"))
      (node (ref "TFT1") (pin "6") (pinfunction "IM0_6") (pintype "bidirectional"))
      (node (ref "U$20") (pin "P1") (pinfunction "GND_P1") (pintype "bidirectional"))
      (node (ref "U$20") (pin "PAD@0") (pinfunction "GND_PAD@0") (pintype "bidirectional"))
      (node (ref "U$20") (pin "PAD@1") (pinfunction "GND_PAD@1") (pintype "bidirectional"))
      (node (ref "U1") (pin "31") (pinfunction "VSS_31") (pintype "bidirectional"))
      (node (ref "U1") (pin "4") (pinfunction "VSS_4") (pintype "bidirectional"))
      (node (ref "U1") (pin "47") (pinfunction "VSS_47") (pintype "bidirectional"))
      (node (ref "U2") (pin "1") (pinfunction "GND_1") (pintype "input"))
      (node (ref "U3") (pin "1") (pinfunction "GND_1") (pintype "bidirectional"))
      (node (ref "X1") (pin "9") (pinfunction "GND_9") (pintype "power_in"))
    )
    (net (code "40") (name "Net-(LED-PadC)") (class "Default")
      (node (ref "LED") (pin "C") (pinfunction "C_C") (pintype "passive"))
      (node (ref "R2") (pin "2") (pinfunction "2_2") (pintype "passive"))
    )
    (net (code "41") (name "Net-(LED1-PadC)") (class "Default")
      (node (ref "LED1") (pin "C") (pinfunction "C_C") (pintype "passive"))
      (node (ref "R6") (pin "2") (pinfunction "2_2") (pintype "passive"))
    )
    (net (code "42") (name "Net-(Q1-B)") (class "Default")
      (node (ref "Q1") (pin "1") (pinfunction "B_1") (pintype "passive"))
      (node (ref "R20") (pin "2") (pinfunction "2_2") (pintype "passive"))
    )
    (net (code "43") (name "Net-(Q1-C)") (class "Default")
      (node (ref "Q1") (pin "3") (pinfunction "C_3") (pintype "passive"))
      (node (ref "R25") (pin "1") (pinfunction "1_1") (pintype "passive"))
      (node (ref "TFT1") (pin "1") (pinfunction "LEDK_1") (pintype "bidirectional"))
    )
    (net (code "44") (name "Net-(R16-Pad2)") (class "Default")
      (node (ref "R16") (pin "2") (pinfunction "2_2") (pintype "passive"))
      (node (ref "TFT1") (pin "2") (pinfunction "LEDA_2") (pintype "bidirectional"))
    )
    (net (code "45") (name "Net-(R17-Pad2)") (class "Default")
      (node (ref "R17") (pin "2") (pinfunction "2_2") (pintype "passive"))
      (node (ref "TFT1") (pin "3") (pinfunction "LEDA_3") (pintype "bidirectional"))
    )
    (net (code "46") (name "Net-(R18-Pad2)") (class "Default")
      (node (ref "R18") (pin "2") (pinfunction "2_2") (pintype "passive"))
      (node (ref "TFT1") (pin "4") (pinfunction "LEDA_4") (pintype "bidirectional"))
    )
    (net (code "47") (name "Net-(R19-Pad2)") (class "Default")
      (node (ref "R19") (pin "2") (pinfunction "2_2") (pintype "passive"))
      (node (ref "TFT1") (pin "5") (pinfunction "LEDA_5") (pintype "bidirectional"))
    )
    (net (code "48") (name "Net-(TFT1-DB0)") (class "Default")
      (node (ref "TFT1") (pin "15") (pinfunction "DB17_15") (pintype "bidirectional"))
      (node (ref "TFT1") (pin "16") (pinfunction "DB16_16") (pintype "bidirectional"))
      (node (ref "TFT1") (pin "17") (pinfunction "DB15_17") (pintype "bidirectional"))
      (node (ref "TFT1") (pin "18") (pinfunction "DB14_18") (pintype "bidirectional"))
      (node (ref "TFT1") (pin "19") (pinfunction "DB13_19") (pintype "bidirectional"))
      (node (ref "TFT1") (pin "20") (pinfunction "DB12_20") (pintype "bidirectional"))
      (node (ref "TFT1") (pin "21") (pinfunction "DB11_21") (pintype "bidirectional"))
      (node (ref "TFT1") (pin "22") (pinfunction "DB10_22") (pintype "bidirectional"))
      (node (ref "TFT1") (pin "23") (pinfunction "DB9_23") (pintype "bidirectional"))
      (node (ref "TFT1") (pin "24") (pinfunction "DB8_24") (pintype "bidirectional"))
      (node (ref "TFT1") (pin "25") (pinfunction "DB7_25") (pintype "bidirectional"))
      (node (ref "TFT1") (pin "26") (pinfunction "DB6_26") (pintype "bidirectional"))
      (node (ref "TFT1") (pin "27") (pinfunction "DB5_27") (pintype "bidirectional"))
      (node (ref "TFT1") (pin "28") (pinfunction "DB4_28") (pintype "bidirectional"))
      (node (ref "TFT1") (pin "29") (pinfunction "DB3_29") (pintype "bidirectional"))
      (node (ref "TFT1") (pin "30") (pinfunction "DB2_30") (pintype "bidirectional"))
      (node (ref "TFT1") (pin "31") (pinfunction "DB1_31") (pintype "bidirectional"))
      (node (ref "TFT1") (pin "32") (pinfunction "DB0_32") (pintype "bidirectional"))
    )
    (net (code "49") (name "Net-(U1-PTA1)") (class "Default")
      (node (ref "R7") (pin "1") (pinfunction "1_1") (pintype "passive"))
      (node (ref "U1") (pin "23") (pinfunction "PTA1_23") (pintype "bidirectional"))
    )
    (net (code "50") (name "Net-(U1-PTA18)") (class "Default")
      (node (ref "U1") (pin "32") (pinfunction "PTA18_32") (pintype "bidirectional"))
      (node (ref "Y2") (pin "3") (pinfunction "2_3") (pintype "passive"))
    )
    (net (code "51") (name "Net-(U1-PTA19)") (class "Default")
      (node (ref "U1") (pin "33") (pinfunction "PTA19_33") (pintype "bidirectional"))
      (node (ref "Y2") (pin "1") (pinfunction "1_1") (pintype "passive"))
    )
    (net (code "52") (name "Net-(U1-PTD6)") (class "Default")
      (node (ref "LED") (pin "A") (pinfunction "A_A") (pintype "passive"))
      (node (ref "U1") (pin "63") (pinfunction "PTD6_63") (pintype "bidirectional"))
    )
    (net (code "53") (name "Net-(U1-PTD7)") (class "Default")
      (node (ref "R14") (pin "1") (pinfunction "1_1") (pintype "passive"))
      (node (ref "U1") (pin "64") (pinfunction "PTD7_64") (pintype "bidirectional"))
    )
    (net (code "54") (name "Net-(U1-VDDA)") (class "Default")
      (node (ref "C5") (pin "1") (pinfunction "1_1") (pintype "passive"))
      (node (ref "L2") (pin "1") (pinfunction "1_1") (pintype "passive"))
      (node (ref "R1") (pin "1") (pinfunction "1_1") (pintype "passive"))
      (node (ref "U1") (pin "13") (pinfunction "VDDA_13") (pintype "bidirectional"))
    )
    (net (code "55") (name "Net-(U1-VREFH)") (class "Default")
      (node (ref "C6") (pin "1") (pinfunction "1_1") (pintype "passive"))
      (node (ref "R1") (pin "2") (pinfunction "2_2") (pintype "passive"))
      (node (ref "U1") (pin "14") (pinfunction "VREFH_14") (pintype "bidirectional"))
    )
    (net (code "56") (name "Net-(U1-VREFL)") (class "Default")
      (node (ref "C5") (pin "2") (pinfunction "2_2") (pintype "passive"))
      (node (ref "C6") (pin "2") (pinfunction "2_2") (pintype "passive"))
      (node (ref "C7") (pin "2") (pinfunction "2_2") (pintype "passive"))
      (node (ref "L1") (pin "2") (pinfunction "2_2") (pintype "passive"))
      (node (ref "U1") (pin "15") (pinfunction "VREFL_15") (pintype "bidirectional"))
      (node (ref "U1") (pin "16") (pinfunction "VSSA_16") (pintype "bidirectional"))
    )
    (net (code "57") (name "Net-(U1-VREF_OUT)") (class "Default")
      (node (ref "C7") (pin "1") (pinfunction "1_1") (pintype "passive"))
      (node (ref "U1") (pin "17") (pinfunction "VREF_OUT_17") (pintype "bidirectional"))
    )
    (net (code "58") (name "Net-(X1-CH_PD)") (class "Default")
      (node (ref "R4") (pin "1") (pinfunction "1_1") (pintype "passive"))
      (node (ref "X1") (pin "3") (pinfunction "CH_PD_3") (pintype "input"))
    )
    (net (code "59") (name "Net-(X1-GPIO2)") (class "Default")
      (node (ref "R3") (pin "1") (pinfunction "1_1") (pintype "passive"))
      (node (ref "X1") (pin "11") (pinfunction "GPIO2_11") (pintype "bidirectional"))
    )
    (net (code "60") (name "Net-(X1-GPIO15)") (class "Default")
      (node (ref "R5") (pin "2") (pinfunction "2_2") (pintype "passive"))
      (node (ref "X1") (pin "10") (pinfunction "GPIO15_10") (pintype "bidirectional"))
    )
    (net (code "61") (name "VCC") (class "Default")
      (node (ref "C11") (pin "1") (pinfunction "1_1") (pintype "passive"))
      (node (ref "C9") (pin "1") (pinfunction "1_1") (pintype "passive"))
      (node (ref "D4") (pin "C") (pinfunction "C_C") (pintype "passive"))
      (node (ref "D5") (pin "C") (pinfunction "C_C") (pintype "passive"))
      (node (ref "U2") (pin "3") (pinfunction "IN_3") (pintype "input"))
    )
    (net (code "62") (name "unconnected-(FTDI-Pad1)") (class "Default")
      (node (ref "FTDI") (pin "1") (pinfunction "1_1") (pintype "passive"))
    )
    (net (code "63") (name "unconnected-(FTDI-Pad5)") (class "Default")
      (node (ref "FTDI") (pin "5") (pinfunction "5_5") (pintype "passive"))
    )
    (net (code "64") (name "unconnected-(J1B-DATA1-Pad8)") (class "Default")
      (node (ref "J1") (pin "8") (pinfunction "DATA1_8") (pintype "bidirectional"))
    )
    (net (code "65") (name "unconnected-(J1B-DATA2-Pad1)") (class "Default")
      (node (ref "J1") (pin "1") (pinfunction "DATA2_1") (pintype "bidirectional"))
    )
    (net (code "66") (name "unconnected-(TFT1-#RD-Pad35)") (class "Default")
      (node (ref "TFT1") (pin "35") (pinfunction "#RD_35") (pintype "bidirectional"))
    )
    (net (code "67") (name "unconnected-(TFT1-DE-Pad14)") (class "Default")
      (node (ref "TFT1") (pin "14") (pinfunction "DE_14") (pintype "bidirectional"))
    )
    (net (code "68") (name "unconnected-(TFT1-DOTCLK-Pad13)") (class "Default")
      (node (ref "TFT1") (pin "13") (pinfunction "DOTCLK_13") (pintype "bidirectional"))
    )
    (net (code "69") (name "unconnected-(TFT1-HSYNC-Pad12)") (class "Default")
      (node (ref "TFT1") (pin "12") (pinfunction "HSYNC_12") (pintype "bidirectional"))
    )
    (net (code "70") (name "unconnected-(TFT1-TE-Pad39)") (class "Default")
      (node (ref "TFT1") (pin "39") (pinfunction "TE_39") (pintype "bidirectional"))
    )
    (net (code "71") (name "unconnected-(TFT1-VSYNC-Pad11)") (class "Default")
      (node (ref "TFT1") (pin "11") (pinfunction "VSYNC_11") (pintype "bidirectional"))
    )
    (net (code "72") (name "unconnected-(TFT1-XL-Pad46)") (class "Default")
      (node (ref "TFT1") (pin "46") (pinfunction "XL_46") (pintype "bidirectional"))
    )
    (net (code "73") (name "unconnected-(TFT1-XR-Pad44)") (class "Default")
      (node (ref "TFT1") (pin "44") (pinfunction "XR_44") (pintype "bidirectional"))
    )
    (net (code "74") (name "unconnected-(TFT1-YD-Pad45)") (class "Default")
      (node (ref "TFT1") (pin "45") (pinfunction "YD_45") (pintype "bidirectional"))
    )
    (net (code "75") (name "unconnected-(TFT1-YU-Pad47)") (class "Default")
      (node (ref "TFT1") (pin "47") (pinfunction "YU_47") (pintype "bidirectional"))
    )
    (net (code "76") (name "unconnected-(U1-ADC0_DM0-Pad10)") (class "Default")
      (node (ref "U1") (pin "10") (pinfunction "ADC0_DM0_10") (pintype "bidirectional"))
    )
    (net (code "77") (name "unconnected-(U1-ADC0_DM3-Pad12)") (class "Default")
      (node (ref "U1") (pin "12") (pinfunction "ADC0_DM3_12") (pintype "bidirectional"))
    )
    (net (code "78") (name "unconnected-(U1-ADC0_DP0-Pad9)") (class "Default")
      (node (ref "U1") (pin "9") (pinfunction "ADC0_DP0_9") (pintype "bidirectional"))
    )
    (net (code "79") (name "unconnected-(U1-ADC0_DP3-Pad11)") (class "Default")
      (node (ref "U1") (pin "11") (pinfunction "ADC0_DP3_11") (pintype "bidirectional"))
    )
    (net (code "80") (name "unconnected-(U1-DAC0-Pad18)") (class "Default")
      (node (ref "U1") (pin "18") (pinfunction "DAC0_18") (pintype "bidirectional"))
    )
    (net (code "81") (name "unconnected-(U1-EXTAL32-Pad20)") (class "Default")
      (node (ref "U1") (pin "20") (pinfunction "EXTAL32_20") (pintype "bidirectional"))
    )
    (net (code "82") (name "unconnected-(U1-PTA2-Pad24)") (class "Default")
      (node (ref "U1") (pin "24") (pinfunction "PTA2_24") (pintype "bidirectional"))
    )
    (net (code "83") (name "unconnected-(U1-PTA4-Pad26)") (class "Default")
      (node (ref "U1") (pin "26") (pinfunction "PTA4_26") (pintype "bidirectional"))
    )
    (net (code "84") (name "unconnected-(U1-PTB19-Pad42)") (class "Default")
      (node (ref "U1") (pin "42") (pinfunction "PTB19_42") (pintype "bidirectional"))
    )
    (net (code "85") (name "unconnected-(U1-USB0_DM-Pad6)") (class "Default")
      (node (ref "U1") (pin "6") (pinfunction "USB0_DM_6") (pintype "bidirectional"))
    )
    (net (code "86") (name "unconnected-(U1-USB0_DP-Pad5)") (class "Default")
      (node (ref "U1") (pin "5") (pinfunction "USB0_DP_5") (pintype "bidirectional"))
    )
    (net (code "87") (name "unconnected-(U1-VREGIN-Pad8)") (class "Default")
      (node (ref "U1") (pin "8") (pinfunction "VREGIN_8") (pintype "bidirectional"))
    )
    (net (code "88") (name "unconnected-(U1-XTAL32-Pad19)") (class "Default")
      (node (ref "U1") (pin "19") (pinfunction "XTAL32_19") (pintype "bidirectional"))
    )
    (net (code "89") (name "unconnected-(X1-ADC-Pad2)") (class "Default")
      (node (ref "X1") (pin "2") (pinfunction "ADC_2") (pintype "passive"))
    )
  )
)
